# Teensy3_based_M_M_board_V2.net
KiCad netlist of a schematic drawn in EAGLE
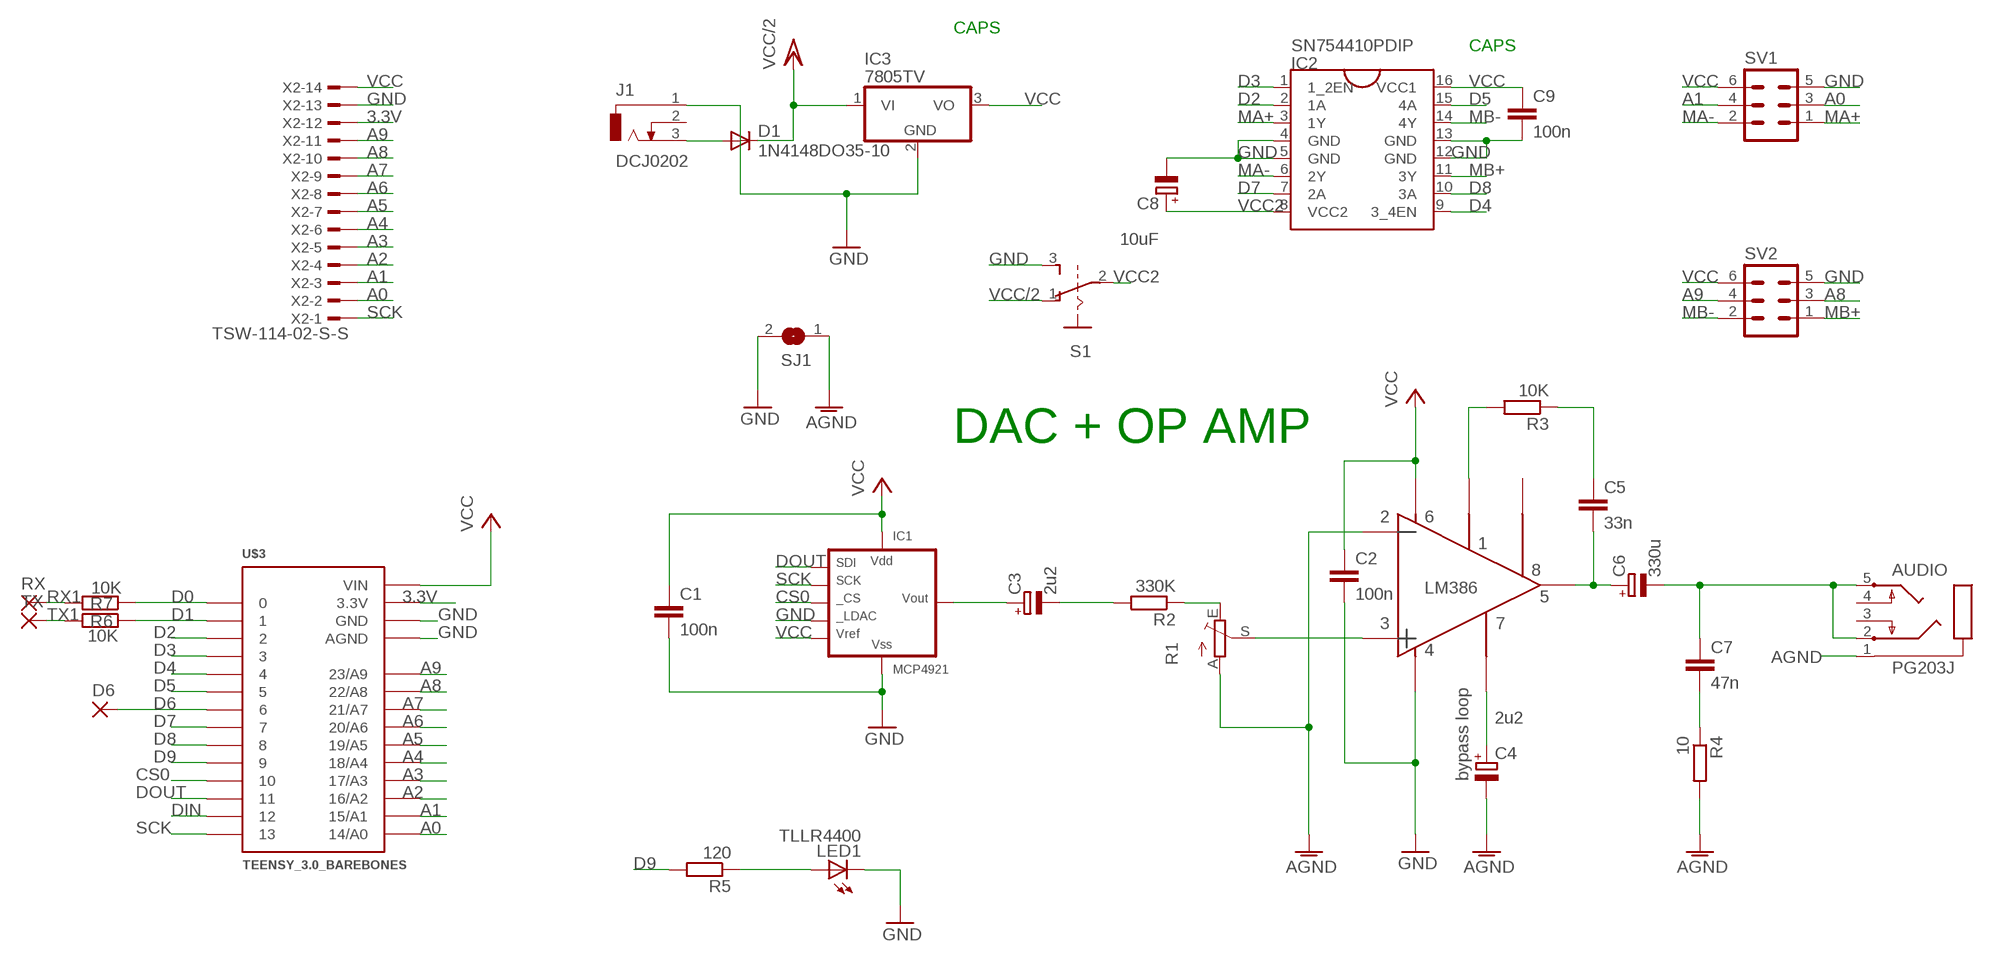
[diagram p0: schematic, sheet 1]

(export (version "E")
  (design (tool "Eeschema 10.0.6"))
  (components
    (comp (ref "AUDIO")
      (value "PG203J")
      (footprint "eagle-import:PG203J")
      (libsource (lib "eagle-import") (part "PG203J"))
    )
    (comp (ref "C1")
      (value "100n")
      (footprint "eagle-import:C050-030X075")
      (libsource (lib "eagle-import") (part "C-EU050-030X075"))
    )
    (comp (ref "C2")
      (value "100n")
      (footprint "eagle-import:C050-030X075")
      (libsource (lib "eagle-import") (part "C-EU050-030X075"))
    )
    (comp (ref "C3")
      (value "2u2")
      (footprint "eagle-import:E2-5")
      (libsource (lib "eagle-import") (part "CPOL-EUE2-5"))
    )
    (comp (ref "C4")
      (value "2u2")
      (footprint "eagle-import:E2-5")
      (libsource (lib "eagle-import") (part "CPOL-EUE2-5"))
    )
    (comp (ref "C5")
      (value "33n")
      (footprint "eagle-import:C050-030X075")
      (libsource (lib "eagle-import") (part "C-EU050-030X075"))
    )
    (comp (ref "C6")
      (value "330u")
      (footprint "eagle-import:E2,5-7")
      (libsource (lib "eagle-import") (part "CPOL-EUE2.5-7"))
    )
    (comp (ref "C7")
      (value "47n")
      (footprint "eagle-import:C050-030X075")
      (libsource (lib "eagle-import") (part "C-EU050-030X075"))
    )
    (comp (ref "C8")
      (value "10uF")
      (footprint "eagle-import:E2-5")
      (libsource (lib "eagle-import") (part "CPOL-EUE2-5"))
    )
    (comp (ref "C9")
      (value "100n")
      (footprint "eagle-import:C050-030X075")
      (libsource (lib "eagle-import") (part "C-EU050-030X075"))
    )
    (comp (ref "D1")
      (value "1N4148DO35-10")
      (footprint "eagle-import:DO35-10")
      (libsource (lib "eagle-import") (part "1N4148DO35-10"))
    )
    (comp (ref "D6")
      (value "2,15/1,0")
      (footprint "eagle-import:2,15_1,0")
      (libsource (lib "eagle-import") (part "2,15/1,0"))
    )
    (comp (ref "IC1")
      (value "MCP4921")
      (footprint "eagle-import:DIL8")
      (libsource (lib "eagle-import") (part "MCP4921P"))
    )
    (comp (ref "IC2")
      (value "SN754410PDIP")
      (footprint "eagle-import:DIL16")
      (libsource (lib "eagle-import") (part "SN754410PDIP"))
    )
    (comp (ref "IC3")
      (value "7805TV")
      (footprint "eagle-import:TO220V")
      (libsource (lib "eagle-import") (part "78TV05"))
    )
    (comp (ref "J1")
      (value "DCJ0202")
      (footprint "eagle-import:DCJ0202")
      (libsource (lib "eagle-import") (part "DCJ0202"))
    )
    (comp (ref "LED1")
      (value "TLLR4400")
      (footprint "eagle-import:LED3MM")
      (fields (field (name "MF") "VISHAY SEMICONDUCTOR"))
      (libsource (lib "eagle-import") (part "TLLR4400"))
    )
    (comp (ref "R1")
      (value "TRIM_EU-CA9V")
      (footprint "eagle-import:CA9V")
      (libsource (lib "eagle-import") (part "TRIM_EU-CA9V"))
    )
    (comp (ref "R2")
      (value "330K")
      (footprint "eagle-import:0207_10")
      (libsource (lib "eagle-import") (part "R-EU_0207/10"))
    )
    (comp (ref "R3")
      (value "10K")
      (footprint "eagle-import:0207_10")
      (libsource (lib "eagle-import") (part "R-EU_0207/10"))
    )
    (comp (ref "R4")
      (value "10")
      (footprint "eagle-import:0207_10")
      (libsource (lib "eagle-import") (part "R-EU_0207/10"))
    )
    (comp (ref "R5")
      (value "120")
      (footprint "eagle-import:0207_10")
      (libsource (lib "eagle-import") (part "R-EU_0207/10"))
    )
    (comp (ref "R6")
      (value "10K")
      (footprint "eagle-import:0207_10")
      (libsource (lib "eagle-import") (part "R-EU_0207/10"))
    )
    (comp (ref "R7")
      (value "10K")
      (footprint "eagle-import:0207_10")
      (libsource (lib "eagle-import") (part "R-EU_0207/10"))
    )
    (comp (ref "RX")
      (value "2,15/1,0")
      (footprint "eagle-import:2,15_1,0")
      (libsource (lib "eagle-import") (part "2,15/1,0"))
    )
    (comp (ref "S1")
      (value "EG1218")
      (footprint "eagle-import:GF-126-0159")
      (libsource (lib "eagle-import") (part "EG1218"))
    )
    (comp (ref "SJ1") (value "SJ") (footprint "eagle-import:SJ") (libsource (lib "eagle-import") (part "SJ")))
    (comp (ref "SV1")
      (value "ML6")
      (footprint "eagle-import:ML6")
      (libsource (lib "eagle-import") (part "ML6"))
    )
    (comp (ref "SV2")
      (value "ML6")
      (footprint "eagle-import:ML6")
      (libsource (lib "eagle-import") (part "ML6"))
    )
    (comp (ref "TX")
      (value "2,15/1,0")
      (footprint "eagle-import:2,15_1,0")
      (libsource (lib "eagle-import") (part "2,15/1,0"))
    )
    (comp (ref "U$2")
      (value "LM386")
      (footprint "eagle-import:LM386")
      (libsource (lib "eagle-import") (part "LM386OA"))
    )
    (comp (ref "U$3")
      (value "TEENSY_3.0_BAREBONES")
      (footprint "eagle-import:TEENSY_3.0_BAREBONES")
      (libsource (lib "eagle-import") (part "TEENSY_3.0_BAREBONES"))
    )
    (comp (ref "X2")
      (value "TSW-114-02-S-S")
      (footprint "eagle-import:TSW-114-02-S-S")
      (libsource (lib "eagle-import") (part "TSW-114-02-S-S"))
    )
  )
  (nets
    (net (code "1") (name "/3.3V") (class "Default")
      (node (ref "U$3") (pin "3.3V") (pinfunction "3.3V_3.3V") (pintype "power_in"))
      (node (ref "X2") (pin "12") (pinfunction "1_12") (pintype "passive"))
    )
    (net (code "2") (name "/A0") (class "Default")
      (node (ref "SV1") (pin "3") (pinfunction "3_3") (pintype "passive"))
      (node (ref "U$3") (pin "14/A0") (pinfunction "14/A0_14/A0") (pintype "bidirectional"))
      (node (ref "X2") (pin "2") (pinfunction "1_2") (pintype "passive"))
    )
    (net (code "3") (name "/A1") (class "Default")
      (node (ref "SV1") (pin "4") (pinfunction "4_4") (pintype "passive"))
      (node (ref "U$3") (pin "15/A1") (pinfunction "15/A1_15/A1") (pintype "bidirectional"))
      (node (ref "X2") (pin "3") (pinfunction "1_3") (pintype "passive"))
    )
    (net (code "4") (name "/A2") (class "Default")
      (node (ref "U$3") (pin "16/A2") (pinfunction "16/A2_16/A2") (pintype "bidirectional"))
      (node (ref "X2") (pin "4") (pinfunction "1_4") (pintype "passive"))
    )
    (net (code "5") (name "/A3") (class "Default")
      (node (ref "U$3") (pin "17/A3") (pinfunction "17/A3_17/A3") (pintype "bidirectional"))
      (node (ref "X2") (pin "5") (pinfunction "1_5") (pintype "passive"))
    )
    (net (code "6") (name "/A4") (class "Default")
      (node (ref "U$3") (pin "18/A4") (pinfunction "18/A4_18/A4") (pintype "bidirectional"))
      (node (ref "X2") (pin "6") (pinfunction "1_6") (pintype "passive"))
    )
    (net (code "7") (name "/A5") (class "Default")
      (node (ref "U$3") (pin "19/A5") (pinfunction "19/A5_19/A5") (pintype "bidirectional"))
      (node (ref "X2") (pin "7") (pinfunction "1_7") (pintype "passive"))
    )
    (net (code "8") (name "/A6") (class "Default")
      (node (ref "U$3") (pin "20/A6") (pinfunction "20/A6_20/A6") (pintype "bidirectional"))
      (node (ref "X2") (pin "8") (pinfunction "1_8") (pintype "passive"))
    )
    (net (code "9") (name "/A7") (class "Default")
      (node (ref "U$3") (pin "21/A7") (pinfunction "21/A7_21/A7") (pintype "bidirectional"))
      (node (ref "X2") (pin "9") (pinfunction "1_9") (pintype "passive"))
    )
    (net (code "10") (name "/A8") (class "Default")
      (node (ref "SV2") (pin "3") (pinfunction "3_3") (pintype "passive"))
      (node (ref "U$3") (pin "22/A8") (pinfunction "22/A8_22/A8") (pintype "bidirectional"))
      (node (ref "X2") (pin "10") (pinfunction "1_10") (pintype "passive"))
    )
    (net (code "11") (name "/A9") (class "Default")
      (node (ref "SV2") (pin "4") (pinfunction "4_4") (pintype "passive"))
      (node (ref "U$3") (pin "23/A9") (pinfunction "23/A9_23/A9") (pintype "bidirectional"))
      (node (ref "X2") (pin "11") (pinfunction "1_11") (pintype "passive"))
    )
    (net (code "12") (name "/CS0") (class "Default")
      (node (ref "IC1") (pin "2") (pinfunction "CS_2") (pintype "input"))
      (node (ref "U$3") (pin "10") (pinfunction "10_10") (pintype "bidirectional"))
    )
    (net (code "13") (name "/D0") (class "Default")
      (node (ref "R7") (pin "1") (pinfunction "1_1") (pintype "passive"))
      (node (ref "U$3") (pin "0") (pinfunction "0_0") (pintype "bidirectional"))
    )
    (net (code "14") (name "/D1") (class "Default")
      (node (ref "R6") (pin "1") (pinfunction "1_1") (pintype "passive"))
      (node (ref "U$3") (pin "1") (pinfunction "1_1") (pintype "bidirectional"))
    )
    (net (code "15") (name "/D2") (class "Default")
      (node (ref "IC2") (pin "2") (pinfunction "1A_2") (pintype "bidirectional"))
      (node (ref "U$3") (pin "2") (pinfunction "2_2") (pintype "bidirectional"))
    )
    (net (code "16") (name "/D3") (class "Default")
      (node (ref "IC2") (pin "1") (pinfunction "1_2EN_1") (pintype "bidirectional"))
      (node (ref "U$3") (pin "3") (pinfunction "3_3") (pintype "bidirectional"))
    )
    (net (code "17") (name "/D4") (class "Default")
      (node (ref "IC2") (pin "9") (pinfunction "3_4EN_9") (pintype "bidirectional"))
      (node (ref "U$3") (pin "4") (pinfunction "4_4") (pintype "bidirectional"))
    )
    (net (code "18") (name "/D5") (class "Default")
      (node (ref "IC2") (pin "15") (pinfunction "4A_15") (pintype "bidirectional"))
      (node (ref "U$3") (pin "5") (pinfunction "5_5") (pintype "bidirectional"))
    )
    (net (code "19") (name "/D6") (class "Default")
      (node (ref "D6") (pin "1") (pinfunction "P_1") (pintype "passive"))
      (node (ref "U$3") (pin "6") (pinfunction "6_6") (pintype "bidirectional"))
    )
    (net (code "20") (name "/D7") (class "Default")
      (node (ref "IC2") (pin "7") (pinfunction "2A_7") (pintype "bidirectional"))
      (node (ref "U$3") (pin "7") (pinfunction "7_7") (pintype "bidirectional"))
    )
    (net (code "21") (name "/D8") (class "Default")
      (node (ref "IC2") (pin "10") (pinfunction "3A_10") (pintype "bidirectional"))
      (node (ref "U$3") (pin "8") (pinfunction "8_8") (pintype "bidirectional"))
    )
    (net (code "22") (name "/D9") (class "Default")
      (node (ref "R5") (pin "2") (pinfunction "2_2") (pintype "passive"))
      (node (ref "U$3") (pin "9") (pinfunction "9_9") (pintype "bidirectional"))
    )
    (net (code "23") (name "/DIN") (class "Default")
      (node (ref "U$3") (pin "12") (pinfunction "12_12") (pintype "bidirectional"))
    )
    (net (code "24") (name "/DOUT") (class "Default")
      (node (ref "IC1") (pin "4") (pinfunction "SDI_4") (pintype "input"))
      (node (ref "U$3") (pin "11") (pinfunction "11_11") (pintype "bidirectional"))
    )
    (net (code "25") (name "/MA+") (class "Default")
      (node (ref "IC2") (pin "3") (pinfunction "1Y_3") (pintype "bidirectional"))
      (node (ref "SV1") (pin "1") (pinfunction "1_1") (pintype "passive"))
    )
    (net (code "26") (name "/MA-") (class "Default")
      (node (ref "IC2") (pin "6") (pinfunction "2Y_6") (pintype "bidirectional"))
      (node (ref "SV1") (pin "2") (pinfunction "2_2") (pintype "passive"))
    )
    (net (code "27") (name "/MB+") (class "Default")
      (node (ref "IC2") (pin "11") (pinfunction "3Y_11") (pintype "bidirectional"))
      (node (ref "SV2") (pin "1") (pinfunction "1_1") (pintype "passive"))
    )
    (net (code "28") (name "/MB-") (class "Default")
      (node (ref "IC2") (pin "14") (pinfunction "4Y_14") (pintype "bidirectional"))
      (node (ref "SV2") (pin "2") (pinfunction "2_2") (pintype "passive"))
    )
    (net (code "29") (name "/RX1") (class "Default")
      (node (ref "R7") (pin "2") (pinfunction "2_2") (pintype "passive"))
      (node (ref "RX") (pin "1") (pinfunction "P_1") (pintype "passive"))
    )
    (net (code "30") (name "/SCK") (class "Default")
      (node (ref "IC1") (pin "3") (pinfunction "SCK_3") (pintype "input"))
      (node (ref "U$3") (pin "13") (pinfunction "13_13") (pintype "bidirectional"))
      (node (ref "X2") (pin "1") (pinfunction "1_1") (pintype "passive"))
    )
    (net (code "31") (name "/TX1") (class "Default")
      (node (ref "R6") (pin "2") (pinfunction "2_2") (pintype "passive"))
      (node (ref "TX") (pin "1") (pinfunction "P_1") (pintype "passive"))
    )
    (net (code "32") (name "/VCC2") (class "Default")
      (node (ref "C8") (pin "+") (pinfunction "+_+") (pintype "passive"))
      (node (ref "IC2") (pin "8") (pinfunction "VCC2_8") (pintype "bidirectional"))
      (node (ref "S1") (pin "2") (pinfunction "02_2") (pintype "passive"))
    )
    (net (code "33") (name "AGND") (class "Default")
      (node (ref "AUDIO") (pin "1") (pinfunction "1_1") (pintype "passive"))
      (node (ref "C4") (pin "-") (pinfunction "-_-") (pintype "passive"))
      (node (ref "R1") (pin "A") (pinfunction "A_A") (pintype "passive"))
      (node (ref "R4") (pin "2") (pinfunction "2_2") (pintype "passive"))
      (node (ref "SJ1") (pin "1") (pinfunction "1_1") (pintype "passive"))
      (node (ref "U$2") (pin "2") (pinfunction "P$2_2") (pintype "bidirectional"))
    )
    (net (code "34") (name "GND") (class "Default")
      (node (ref "C1") (pin "2") (pinfunction "2_2") (pintype "passive"))
      (node (ref "C2") (pin "2") (pinfunction "2_2") (pintype "passive"))
      (node (ref "C8") (pin "-") (pinfunction "-_-") (pintype "passive"))
      (node (ref "C9") (pin "2") (pinfunction "2_2") (pintype "passive"))
      (node (ref "IC1") (pin "5") (pinfunction "LDAC_5") (pintype "input"))
      (node (ref "IC1") (pin "7") (pinfunction "VSS_7") (pintype "power_in"))
      (node (ref "IC2") (pin "12") (pinfunction "GND_12") (pintype "bidirectional"))
      (node (ref "IC2") (pin "13") (pinfunction "GND_13") (pintype "bidirectional"))
      (node (ref "IC2") (pin "4") (pinfunction "GND_4") (pintype "bidirectional"))
      (node (ref "IC2") (pin "5") (pinfunction "GND_5") (pintype "bidirectional"))
      (node (ref "IC3") (pin "2") (pinfunction "GND_2") (pintype "passive"))
      (node (ref "J1") (pin "1") (pinfunction "1_1") (pintype "passive"))
      (node (ref "LED1") (pin "K") (pinfunction "C_K") (pintype "passive"))
      (node (ref "S1") (pin "3") (pinfunction "3_3") (pintype "passive"))
      (node (ref "SJ1") (pin "2") (pinfunction "2_2") (pintype "passive"))
      (node (ref "SV1") (pin "5") (pinfunction "5_5") (pintype "passive"))
      (node (ref "SV2") (pin "5") (pinfunction "5_5") (pintype "passive"))
      (node (ref "U$2") (pin "4") (pinfunction "P$4_4") (pintype "bidirectional"))
      (node (ref "U$3") (pin "AGND") (pinfunction "AGND_AGND") (pintype "power_in"))
      (node (ref "U$3") (pin "GND") (pinfunction "GND_GND") (pintype "power_in"))
      (node (ref "X2") (pin "13") (pinfunction "1_13") (pintype "passive"))
    )
    (net (code "35") (name "Net-(AUDIO-Pad2)") (class "Default")
      (node (ref "AUDIO") (pin "2") (pinfunction "2_2") (pintype "passive"))
      (node (ref "AUDIO") (pin "5") (pinfunction "5_5") (pintype "passive"))
      (node (ref "C6") (pin "-") (pinfunction "-_-") (pintype "passive"))
      (node (ref "C7") (pin "1") (pinfunction "1_1") (pintype "passive"))
    )
    (net (code "36") (name "Net-(C3-Pad-)") (class "Default")
      (node (ref "C3") (pin "-") (pinfunction "-_-") (pintype "passive"))
      (node (ref "R2") (pin "2") (pinfunction "2_2") (pintype "passive"))
    )
    (net (code "37") (name "Net-(C5-Pad1)") (class "Default")
      (node (ref "C5") (pin "1") (pinfunction "1_1") (pintype "passive"))
      (node (ref "R3") (pin "1") (pinfunction "1_1") (pintype "passive"))
    )
    (net (code "38") (name "Net-(C7-Pad2)") (class "Default")
      (node (ref "C7") (pin "2") (pinfunction "2_2") (pintype "passive"))
      (node (ref "R4") (pin "1") (pinfunction "1_1") (pintype "passive"))
    )
    (net (code "39") (name "Net-(D1-PadA)") (class "Default")
      (node (ref "D1") (pin "A") (pinfunction "A_A") (pintype "passive"))
      (node (ref "J1") (pin "3") (pinfunction "3_3") (pintype "passive"))
    )
    (net (code "40") (name "Net-(IC1-VOUT)") (class "Default")
      (node (ref "C3") (pin "+") (pinfunction "+_+") (pintype "passive"))
      (node (ref "IC1") (pin "8") (pinfunction "VOUT_8") (pintype "output"))
    )
    (net (code "41") (name "Net-(LED1-PadA)") (class "Default")
      (node (ref "LED1") (pin "A") (pinfunction "A_A") (pintype "passive"))
      (node (ref "R5") (pin "1") (pinfunction "1_1") (pintype "passive"))
    )
    (net (code "42") (name "Net-(R1-PadE)") (class "Default")
      (node (ref "R1") (pin "E") (pinfunction "E_E") (pintype "passive"))
      (node (ref "R2") (pin "1") (pinfunction "1_1") (pintype "passive"))
    )
    (net (code "43") (name "Net-(U$2-P$1)") (class "Default")
      (node (ref "R3") (pin "2") (pinfunction "2_2") (pintype "passive"))
      (node (ref "U$2") (pin "1") (pinfunction "P$1_1") (pintype "bidirectional"))
    )
    (net (code "44") (name "Net-(U$2-P$3)") (class "Default")
      (node (ref "R1") (pin "S") (pinfunction "S_S") (pintype "passive"))
      (node (ref "U$2") (pin "3") (pinfunction "P$3_3") (pintype "bidirectional"))
    )
    (net (code "45") (name "Net-(U$2-P$5)") (class "Default")
      (node (ref "C5") (pin "2") (pinfunction "2_2") (pintype "passive"))
      (node (ref "C6") (pin "+") (pinfunction "+_+") (pintype "passive"))
      (node (ref "U$2") (pin "5") (pinfunction "P$5_5") (pintype "bidirectional"))
    )
    (net (code "46") (name "Net-(U$2-P$7)") (class "Default")
      (node (ref "C4") (pin "+") (pinfunction "+_+") (pintype "passive"))
      (node (ref "U$2") (pin "7") (pinfunction "P$7_7") (pintype "bidirectional"))
    )
    (net (code "47") (name "VCC") (class "Default")
      (node (ref "C1") (pin "1") (pinfunction "1_1") (pintype "passive"))
      (node (ref "C2") (pin "1") (pinfunction "1_1") (pintype "passive"))
      (node (ref "C9") (pin "1") (pinfunction "1_1") (pintype "passive"))
      (node (ref "IC1") (pin "1") (pinfunction "VDD_1") (pintype "power_in"))
      (node (ref "IC1") (pin "6") (pinfunction "VREF_6") (pintype "input"))
      (node (ref "IC2") (pin "16") (pinfunction "VCC1_16") (pintype "bidirectional"))
      (node (ref "IC3") (pin "3") (pinfunction "VO_3") (pintype "passive"))
      (node (ref "SV1") (pin "6") (pinfunction "6_6") (pintype "passive"))
      (node (ref "SV2") (pin "6") (pinfunction "6_6") (pintype "passive"))
      (node (ref "U$2") (pin "6") (pinfunction "P$6_6") (pintype "bidirectional"))
      (node (ref "U$3") (pin "VIN") (pinfunction "VIN_VIN") (pintype "power_in"))
      (node (ref "X2") (pin "14") (pinfunction "1_14") (pintype "passive"))
    )
    (net (code "48") (name "VCC{slash}2") (class "Default")
      (node (ref "D1") (pin "C") (pinfunction "C_C") (pintype "passive"))
      (node (ref "IC3") (pin "1") (pinfunction "VI_1") (pintype "input"))
      (node (ref "S1") (pin "1") (pinfunction "1_1") (pintype "passive"))
    )
    (net (code "49") (name "unconnected-(AUDIO-Pad3)") (class "Default")
      (node (ref "AUDIO") (pin "3") (pinfunction "3_3") (pintype "passive"))
    )
    (net (code "50") (name "unconnected-(AUDIO-Pad4)") (class "Default")
      (node (ref "AUDIO") (pin "4") (pinfunction "4_4") (pintype "passive"))
    )
    (net (code "51") (name "unconnected-(J1-Pad2)") (class "Default")
      (node (ref "J1") (pin "2") (pinfunction "2_2") (pintype "passive"))
    )
    (net (code "52") (name "unconnected-(U$2-P$8-Pad8)") (class "Default")
      (node (ref "U$2") (pin "8") (pinfunction "P$8_8") (pintype "bidirectional"))
    )
  )
)
